# anbisonique2.net
KiCad netlist of a schematic drawn in EAGLE
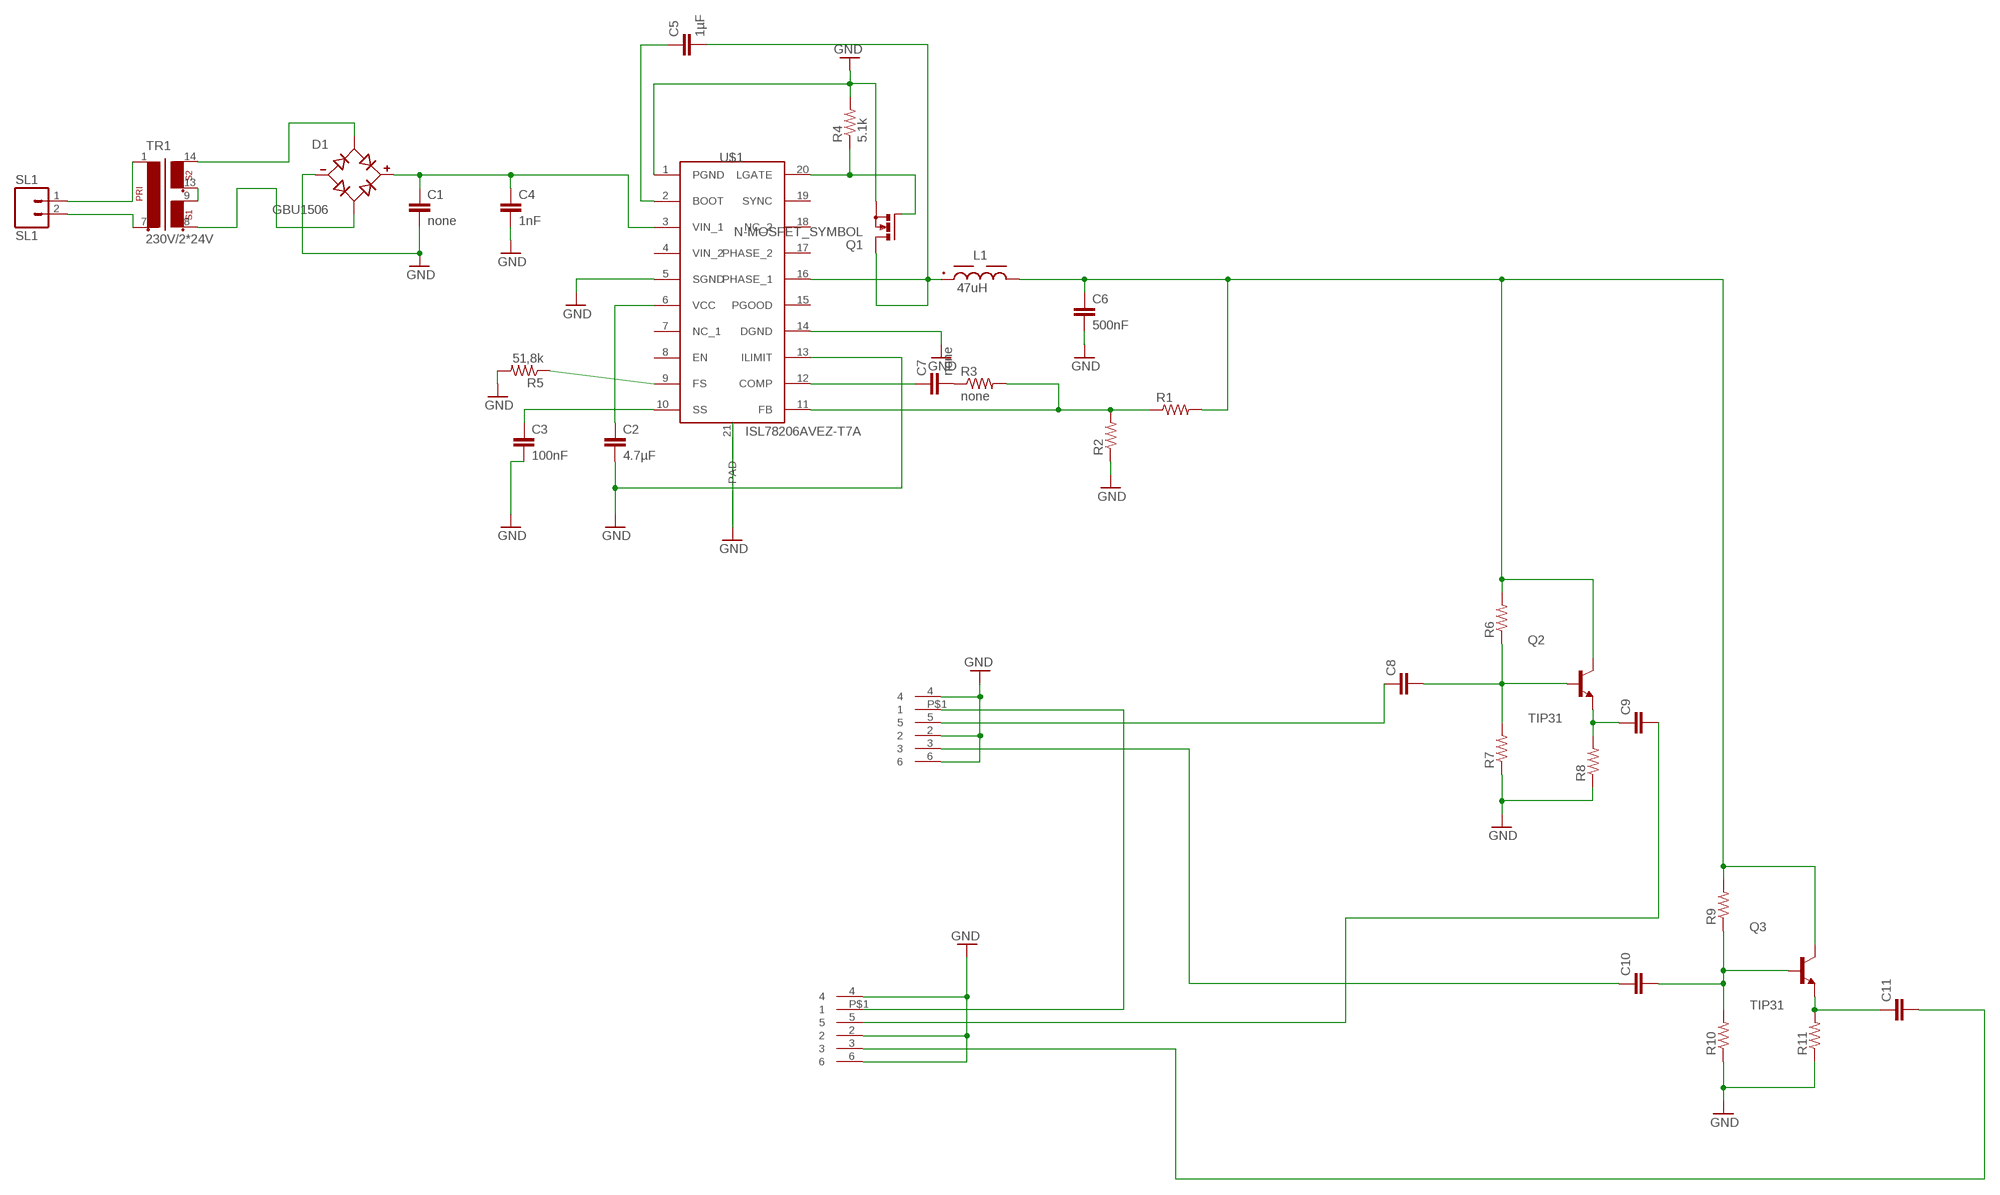
[diagram p0: schematic, sheet 1]

(export (version "E")
  (design (tool "Eeschema 10.0.6"))
  (components
    (comp (ref "C1")
      (value "none")
      (footprint "eagle-import:C0603")
      (libsource (lib "eagle-import") (part "C-EUC0603"))
    )
    (comp (ref "C2")
      (value "4.7µF")
      (footprint "eagle-import:C0603")
      (libsource (lib "eagle-import") (part "C-EUC0603"))
    )
    (comp (ref "C3")
      (value "100nF")
      (footprint "eagle-import:C0603")
      (libsource (lib "eagle-import") (part "C-EUC0603"))
    )
    (comp (ref "C4")
      (value "1nF")
      (footprint "eagle-import:C0603")
      (libsource (lib "eagle-import") (part "C-EUC0603"))
    )
    (comp (ref "C5")
      (value "1µF")
      (footprint "eagle-import:C0603")
      (libsource (lib "eagle-import") (part "C-EUC0603"))
    )
    (comp (ref "C6")
      (value "500nF")
      (footprint "eagle-import:C0603")
      (libsource (lib "eagle-import") (part "C-EUC0603"))
    )
    (comp (ref "C7")
      (value "none")
      (footprint "eagle-import:C0603")
      (libsource (lib "eagle-import") (part "C-EUC0603"))
    )
    (comp (ref "C8")
      (value "C-EUC0603")
      (footprint "eagle-import:C0603")
      (libsource (lib "eagle-import") (part "C-EUC0603"))
    )
    (comp (ref "C9")
      (value "C-EUC0603")
      (footprint "eagle-import:C0603")
      (libsource (lib "eagle-import") (part "C-EUC0603"))
    )
    (comp (ref "C10")
      (value "C-EUC0603")
      (footprint "eagle-import:C0603")
      (libsource (lib "eagle-import") (part "C-EUC0603"))
    )
    (comp (ref "C11")
      (value "C-EUC0603")
      (footprint "eagle-import:C0603")
      (libsource (lib "eagle-import") (part "C-EUC0603"))
    )
    (comp (ref "D1")
      (value "GBU1506")
      (footprint "eagle-import:SIP343W114P508L2205H2134Q4")
      (fields (field (name "MF") "Taiwan Semiconductor Corporation"))
      (libsource (lib "eagle-import") (part "GBU1506"))
    )
    (comp (ref "L1")
      (value "47uH")
      (footprint "eagle-import:WE-PDA_1210")
      (libsource (lib "eagle-import") (part "WE-PDA_1210_7847709470"))
    )
    (comp (ref "Q2")
      (value "TIP31")
      (footprint "eagle-import:TO254P1060X482X2222-3")
      (fields (field (name "MF") "ON"))
      (libsource (lib "eagle-import") (part "TIP31"))
    )
    (comp (ref "Q3")
      (value "TIP31")
      (footprint "eagle-import:TO254P1060X482X2222-3")
      (fields (field (name "MF") "ON"))
      (libsource (lib "eagle-import") (part "TIP31"))
    )
    (comp (ref "R1")
      (value "R-US_R0603")
      (footprint "eagle-import:R0603")
      (libsource (lib "eagle-import") (part "R-US_R0603"))
    )
    (comp (ref "R2")
      (value "R-US_R0603")
      (footprint "eagle-import:R0603")
      (libsource (lib "eagle-import") (part "R-US_R0603"))
    )
    (comp (ref "R3")
      (value "none")
      (footprint "eagle-import:R0603")
      (libsource (lib "eagle-import") (part "R-US_R0603"))
    )
    (comp (ref "R4")
      (value "5.1k")
      (footprint "eagle-import:R0603")
      (libsource (lib "eagle-import") (part "R-US_R0603"))
    )
    (comp (ref "R5")
      (value "51,8k")
      (footprint "eagle-import:R0603")
      (libsource (lib "eagle-import") (part "R-US_R0603"))
    )
    (comp (ref "R6")
      (value "R-US_R0603")
      (footprint "eagle-import:R0603")
      (libsource (lib "eagle-import") (part "R-US_R0603"))
    )
    (comp (ref "R7")
      (value "R-US_R0603")
      (footprint "eagle-import:R0603")
      (libsource (lib "eagle-import") (part "R-US_R0603"))
    )
    (comp (ref "R8")
      (value "R-US_R0603")
      (footprint "eagle-import:R0603")
      (libsource (lib "eagle-import") (part "R-US_R0603"))
    )
    (comp (ref "R9")
      (value "R-US_R0603")
      (footprint "eagle-import:R0603")
      (libsource (lib "eagle-import") (part "R-US_R0603"))
    )
    (comp (ref "R10")
      (value "R-US_R0603")
      (footprint "eagle-import:R0603")
      (libsource (lib "eagle-import") (part "R-US_R0603"))
    )
    (comp (ref "R11")
      (value "R-US_R0603")
      (footprint "eagle-import:R0603")
      (libsource (lib "eagle-import") (part "R-US_R0603"))
    )
    (comp (ref "SL1")
      (value "SL1")
      (footprint "eagle-import:02P")
      (libsource (lib "eagle-import") (part "M02"))
    )
    (comp (ref "TR1")
      (value "230V/2*24V")
      (footprint "eagle-import:EI60-2")
      (libsource (lib "eagle-import") (part "EI60-2"))
    )
    (comp (ref "U$1")
      (value "ISL78206AVEZ-T7A")
      (footprint "eagle-import:SOP65P640X110-21N")
      (libsource (lib "eagle-import") (part "ISL78206AVEZ-T7A"))
    )
    (comp (ref "U$2")
      (value "JACK6.35MMRSPRODEV")
      (footprint "eagle-import:JACKRSPRO6.35MM")
      (libsource (lib "eagle-import") (part "JACK6.35MMRSPRODEV"))
    )
    (comp (ref "U$3")
      (value "JACK6.35MMRSPRODEV")
      (footprint "eagle-import:JACKRSPRO6.35MM")
      (libsource (lib "eagle-import") (part "JACK6.35MMRSPRODEV"))
    )
  )
  (nets
    (net (code "1") (name "GND") (class "Default")
      (node (ref "C1") (pin "2") (pinfunction "2_2") (pintype "passive"))
      (node (ref "C2") (pin "2") (pinfunction "2_2") (pintype "passive"))
      (node (ref "C3") (pin "2") (pinfunction "2_2") (pintype "passive"))
      (node (ref "C4") (pin "2") (pinfunction "2_2") (pintype "passive"))
      (node (ref "C6") (pin "2") (pinfunction "2_2") (pintype "passive"))
      (node (ref "D1") (pin "-") (pinfunction "-_-") (pintype "passive"))
      (node (ref "R10") (pin "1") (pinfunction "1_1") (pintype "passive"))
      (node (ref "R11") (pin "1") (pinfunction "1_1") (pintype "passive"))
      (node (ref "R2") (pin "1") (pinfunction "1_1") (pintype "passive"))
      (node (ref "R4") (pin "2") (pinfunction "2_2") (pintype "passive"))
      (node (ref "R5") (pin "2") (pinfunction "2_2") (pintype "passive"))
      (node (ref "R7") (pin "1") (pinfunction "1_1") (pintype "passive"))
      (node (ref "R8") (pin "1") (pinfunction "1_1") (pintype "passive"))
      (node (ref "U$1") (pin "1") (pinfunction "PGND_1") (pintype "bidirectional"))
      (node (ref "U$1") (pin "13") (pinfunction "ILIMIT_13") (pintype "bidirectional"))
      (node (ref "U$1") (pin "14") (pinfunction "DGND_14") (pintype "bidirectional"))
      (node (ref "U$1") (pin "21") (pinfunction "PAD_21") (pintype "bidirectional"))
      (node (ref "U$1") (pin "5") (pinfunction "SGND_5") (pintype "bidirectional"))
      (node (ref "U$2") (pin "2") (pinfunction "2_2") (pintype "bidirectional"))
      (node (ref "U$2") (pin "4") (pinfunction "4_4") (pintype "bidirectional"))
      (node (ref "U$2") (pin "6") (pinfunction "6_6") (pintype "bidirectional"))
      (node (ref "U$3") (pin "2") (pinfunction "2_2") (pintype "bidirectional"))
      (node (ref "U$3") (pin "4") (pinfunction "4_4") (pintype "bidirectional"))
      (node (ref "U$3") (pin "6") (pinfunction "6_6") (pintype "bidirectional"))
    )
    (net (code "2") (name "Net-(C7-Pad2)") (class "Default")
      (node (ref "C7") (pin "2") (pinfunction "2_2") (pintype "passive"))
      (node (ref "R3") (pin "1") (pinfunction "1_1") (pintype "passive"))
    )
    (net (code "3") (name "Net-(C8-Pad1)") (class "Default")
      (node (ref "C8") (pin "1") (pinfunction "1_1") (pintype "passive"))
      (node (ref "U$2") (pin "5") (pinfunction "5_5") (pintype "bidirectional"))
    )
    (net (code "4") (name "Net-(C9-Pad2)") (class "Default")
      (node (ref "C9") (pin "2") (pinfunction "2_2") (pintype "passive"))
      (node (ref "U$3") (pin "5") (pinfunction "5_5") (pintype "bidirectional"))
    )
    (net (code "5") (name "Net-(C10-Pad1)") (class "Default")
      (node (ref "C10") (pin "1") (pinfunction "1_1") (pintype "passive"))
      (node (ref "U$2") (pin "3") (pinfunction "3_3") (pintype "bidirectional"))
    )
    (net (code "6") (name "Net-(C11-Pad2)") (class "Default")
      (node (ref "C11") (pin "2") (pinfunction "2_2") (pintype "passive"))
      (node (ref "U$3") (pin "3") (pinfunction "3_3") (pintype "bidirectional"))
    )
    (net (code "7") (name "Net-(Q2-B)") (class "Default")
      (node (ref "C8") (pin "2") (pinfunction "2_2") (pintype "passive"))
      (node (ref "Q2") (pin "1") (pinfunction "B_1") (pintype "passive"))
      (node (ref "R6") (pin "1") (pinfunction "1_1") (pintype "passive"))
      (node (ref "R7") (pin "2") (pinfunction "2_2") (pintype "passive"))
    )
    (net (code "8") (name "Net-(Q2-C)") (class "Default")
      (node (ref "C6") (pin "1") (pinfunction "1_1") (pintype "passive"))
      (node (ref "L1") (pin "2") (pinfunction "2_2") (pintype "passive"))
      (node (ref "Q2") (pin "2") (pinfunction "C_2") (pintype "passive"))
      (node (ref "Q3") (pin "2") (pinfunction "C_2") (pintype "passive"))
      (node (ref "R1") (pin "2") (pinfunction "2_2") (pintype "passive"))
      (node (ref "R6") (pin "2") (pinfunction "2_2") (pintype "passive"))
      (node (ref "R9") (pin "2") (pinfunction "2_2") (pintype "passive"))
    )
    (net (code "9") (name "Net-(Q2-E)") (class "Default")
      (node (ref "C9") (pin "1") (pinfunction "1_1") (pintype "passive"))
      (node (ref "Q2") (pin "3") (pinfunction "E_3") (pintype "passive"))
      (node (ref "R8") (pin "2") (pinfunction "2_2") (pintype "passive"))
    )
    (net (code "10") (name "Net-(Q3-B)") (class "Default")
      (node (ref "C10") (pin "2") (pinfunction "2_2") (pintype "passive"))
      (node (ref "Q3") (pin "1") (pinfunction "B_1") (pintype "passive"))
      (node (ref "R10") (pin "2") (pinfunction "2_2") (pintype "passive"))
      (node (ref "R9") (pin "1") (pinfunction "1_1") (pintype "passive"))
    )
    (net (code "11") (name "Net-(Q3-E)") (class "Default")
      (node (ref "C11") (pin "1") (pinfunction "1_1") (pintype "passive"))
      (node (ref "Q3") (pin "3") (pinfunction "E_3") (pintype "passive"))
      (node (ref "R11") (pin "2") (pinfunction "2_2") (pintype "passive"))
    )
    (net (code "12") (name "Net-(SL1-Pad1)") (class "Default")
      (node (ref "SL1") (pin "1") (pinfunction "1_1") (pintype "passive"))
      (node (ref "TR1") (pin "1") (pinfunction "1_1") (pintype "passive"))
    )
    (net (code "13") (name "Net-(TR1-2)") (class "Default")
      (node (ref "SL1") (pin "2") (pinfunction "2_2") (pintype "passive"))
      (node (ref "TR1") (pin "7") (pinfunction "2_7") (pintype "passive"))
    )
    (net (code "14") (name "Net-(TR1-3)") (class "Default")
      (node (ref "D1") (pin "AC2") (pinfunction "AC2_AC2") (pintype "passive"))
      (node (ref "TR1") (pin "8") (pinfunction "3_8") (pintype "passive"))
    )
    (net (code "15") (name "Net-(TR1-4)") (class "Default")
      (node (ref "TR1") (pin "13") (pinfunction "5_13") (pintype "passive"))
      (node (ref "TR1") (pin "9") (pinfunction "4_9") (pintype "passive"))
    )
    (net (code "16") (name "Net-(TR1-6)") (class "Default")
      (node (ref "D1") (pin "AC1") (pinfunction "AC1_AC1") (pintype "passive"))
      (node (ref "TR1") (pin "14") (pinfunction "6_14") (pintype "passive"))
    )
    (net (code "17") (name "Net-(U$1-BOOT)") (class "Default")
      (node (ref "C5") (pin "1") (pinfunction "1_1") (pintype "passive"))
      (node (ref "U$1") (pin "2") (pinfunction "BOOT_2") (pintype "bidirectional"))
    )
    (net (code "18") (name "Net-(U$1-COMP)") (class "Default")
      (node (ref "C7") (pin "1") (pinfunction "1_1") (pintype "passive"))
      (node (ref "U$1") (pin "12") (pinfunction "COMP_12") (pintype "bidirectional"))
    )
    (net (code "19") (name "Net-(U$1-FB)") (class "Default")
      (node (ref "R1") (pin "1") (pinfunction "1_1") (pintype "passive"))
      (node (ref "R2") (pin "2") (pinfunction "2_2") (pintype "passive"))
      (node (ref "R3") (pin "2") (pinfunction "2_2") (pintype "passive"))
      (node (ref "U$1") (pin "11") (pinfunction "FB_11") (pintype "bidirectional"))
    )
    (net (code "20") (name "Net-(U$1-FS)") (class "Default")
      (node (ref "R5") (pin "1") (pinfunction "1_1") (pintype "passive"))
      (node (ref "U$1") (pin "9") (pinfunction "FS_9") (pintype "bidirectional"))
    )
    (net (code "21") (name "Net-(U$1-LGATE)") (class "Default")
      (node (ref "R4") (pin "1") (pinfunction "1_1") (pintype "passive"))
      (node (ref "U$1") (pin "20") (pinfunction "LGATE_20") (pintype "bidirectional"))
    )
    (net (code "22") (name "Net-(U$1-PHASE_1)") (class "Default")
      (node (ref "C5") (pin "2") (pinfunction "2_2") (pintype "passive"))
      (node (ref "L1") (pin "1") (pinfunction "1_1") (pintype "passive"))
      (node (ref "U$1") (pin "16") (pinfunction "PHASE_1_16") (pintype "bidirectional"))
    )
    (net (code "23") (name "Net-(U$1-SS)") (class "Default")
      (node (ref "C3") (pin "1") (pinfunction "1_1") (pintype "passive"))
      (node (ref "U$1") (pin "10") (pinfunction "SS_10") (pintype "bidirectional"))
    )
    (net (code "24") (name "Net-(U$1-VCC)") (class "Default")
      (node (ref "C2") (pin "1") (pinfunction "1_1") (pintype "passive"))
      (node (ref "U$1") (pin "6") (pinfunction "VCC_6") (pintype "bidirectional"))
    )
    (net (code "25") (name "Net-(U$1-VIN_1)") (class "Default")
      (node (ref "C1") (pin "1") (pinfunction "1_1") (pintype "passive"))
      (node (ref "C4") (pin "1") (pinfunction "1_1") (pintype "passive"))
      (node (ref "D1") (pin "+") (pinfunction "+_+") (pintype "passive"))
      (node (ref "U$1") (pin "3") (pinfunction "VIN_1_3") (pintype "bidirectional"))
    )
    (net (code "26") (name "Net-(U$2-1)") (class "Default")
      (node (ref "U$2") (pin "P$1") (pinfunction "1_P$1") (pintype "bidirectional"))
      (node (ref "U$3") (pin "P$1") (pinfunction "1_P$1") (pintype "bidirectional"))
    )
    (net (code "27") (name "unconnected-(U$1-EN-Pad8)") (class "Default")
      (node (ref "U$1") (pin "8") (pinfunction "EN_8") (pintype "bidirectional"))
    )
    (net (code "28") (name "unconnected-(U$1-NC_1-Pad7)") (class "Default")
      (node (ref "U$1") (pin "7") (pinfunction "NC_1_7") (pintype "bidirectional"))
    )
    (net (code "29") (name "unconnected-(U$1-NC_2-Pad18)") (class "Default")
      (node (ref "U$1") (pin "18") (pinfunction "NC_2_18") (pintype "bidirectional"))
    )
    (net (code "30") (name "unconnected-(U$1-PGOOD-Pad15)") (class "Default")
      (node (ref "U$1") (pin "15") (pinfunction "PGOOD_15") (pintype "bidirectional"))
    )
    (net (code "31") (name "unconnected-(U$1-PHASE_2-Pad17)") (class "Default")
      (node (ref "U$1") (pin "17") (pinfunction "PHASE_2_17") (pintype "bidirectional"))
    )
    (net (code "32") (name "unconnected-(U$1-SYNC-Pad19)") (class "Default")
      (node (ref "U$1") (pin "19") (pinfunction "SYNC_19") (pintype "bidirectional"))
    )
    (net (code "33") (name "unconnected-(U$1-VIN_2-Pad4)") (class "Default")
      (node (ref "U$1") (pin "4") (pinfunction "VIN_2_4") (pintype "bidirectional"))
    )
  )
)
